# Sheet1.net
KiCad netlist of a schematic drawn in Altium Designer
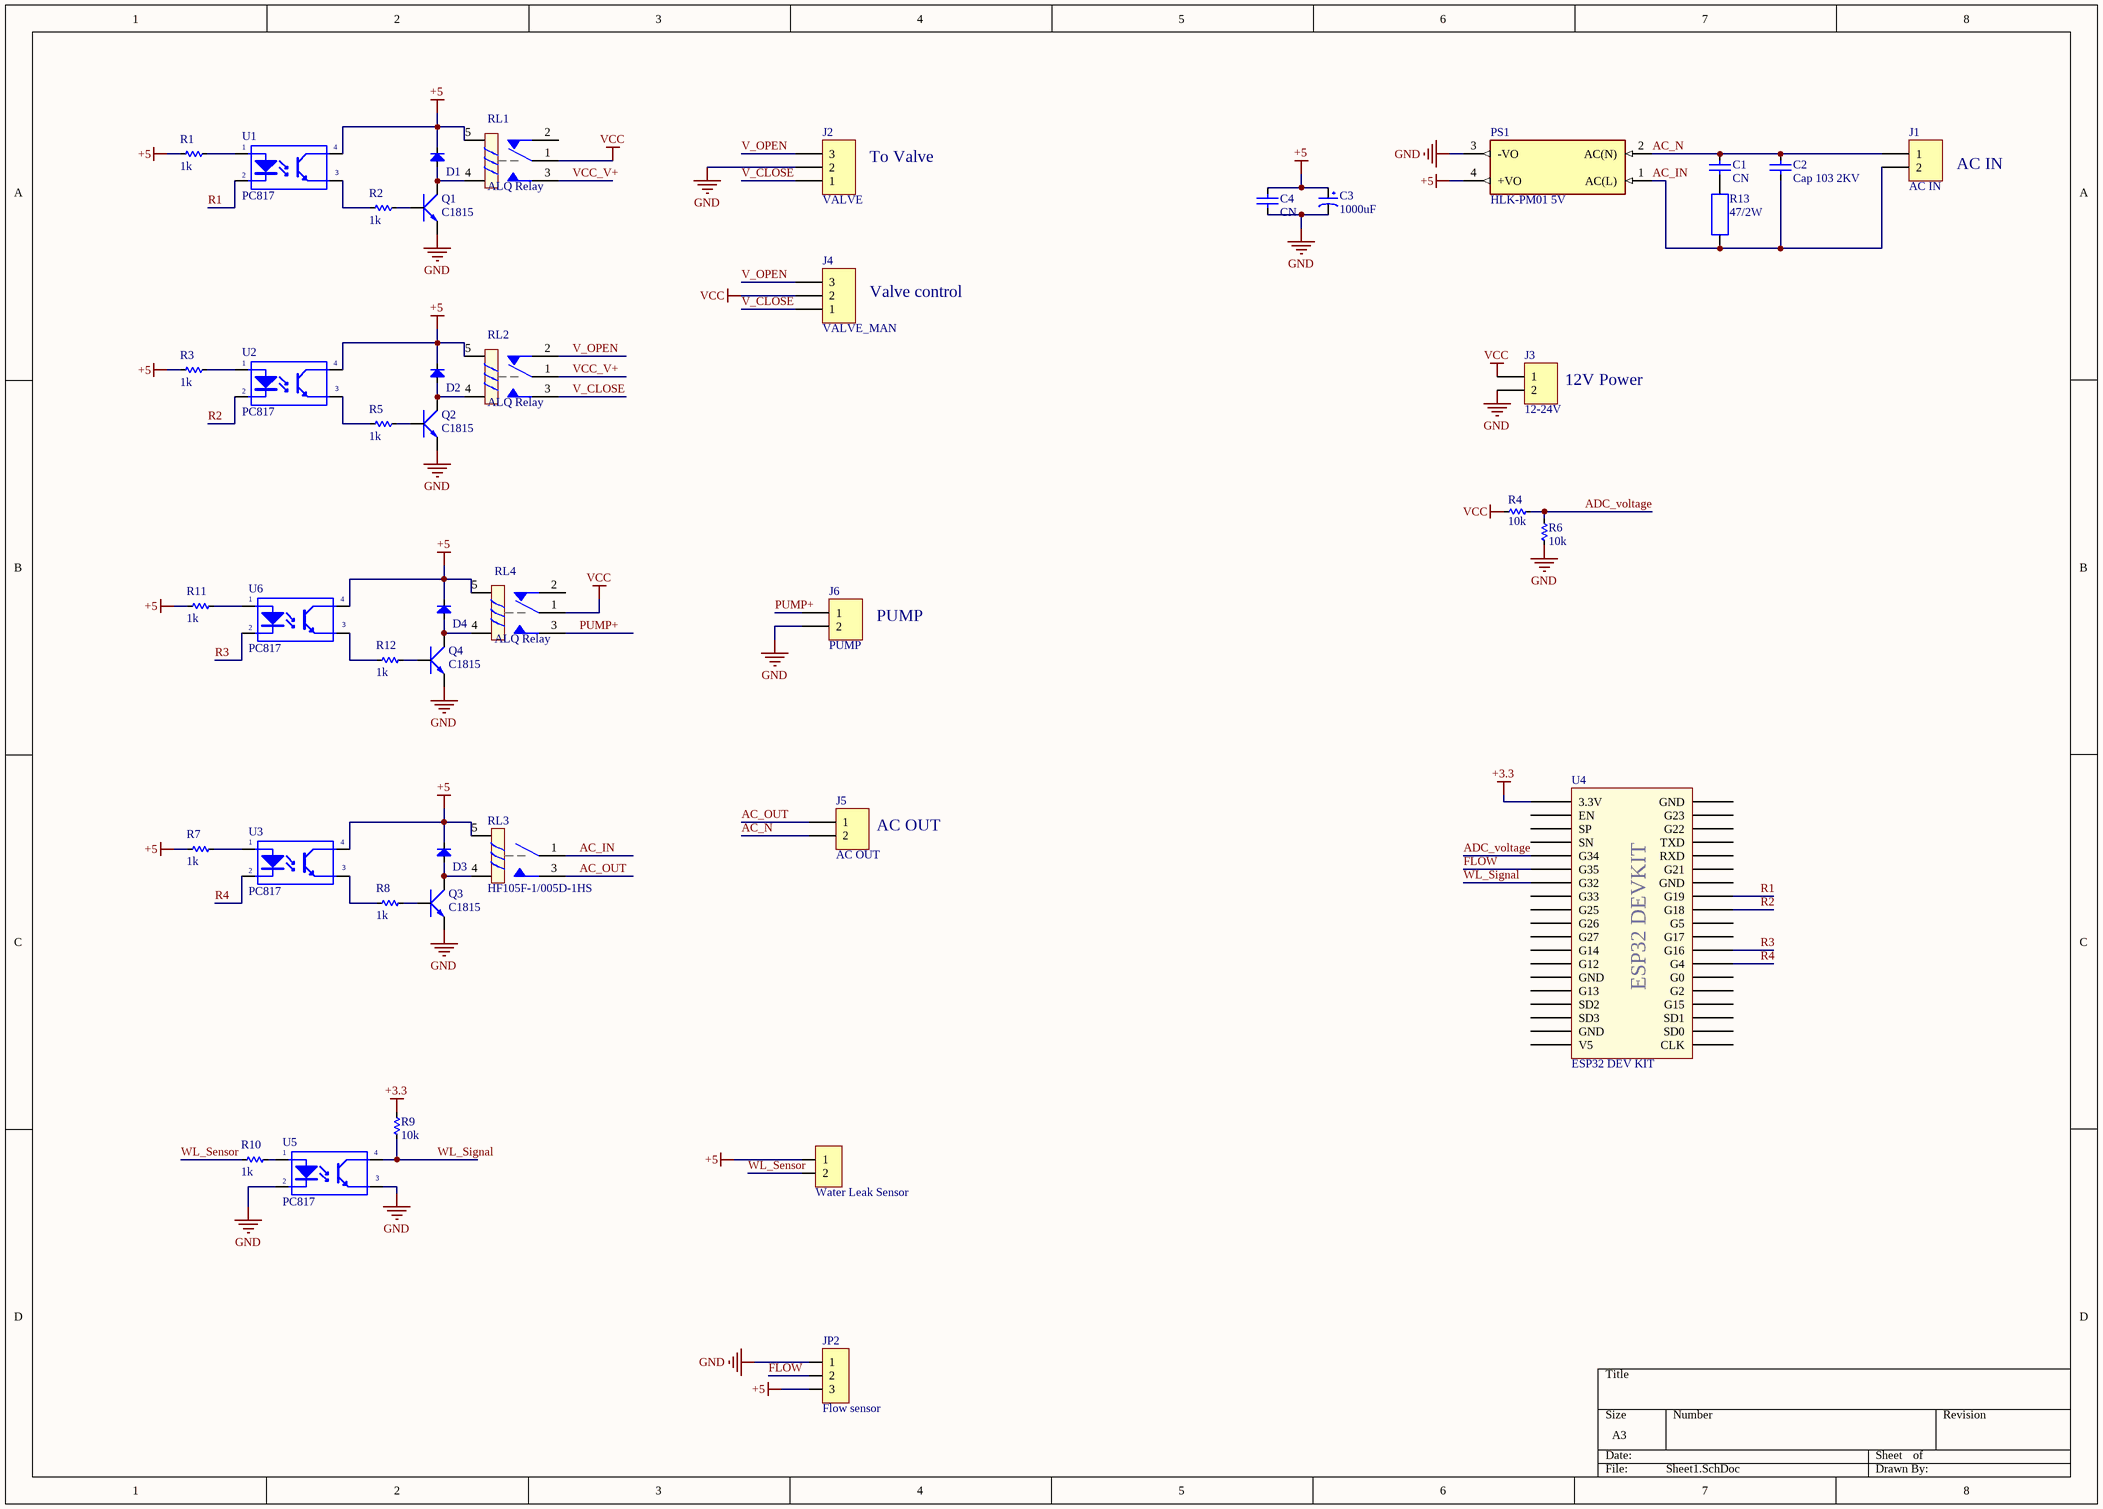
[diagram p0: Sheet1.SchDoc]

(export (version "E")
  (design (tool "Eeschema 10.0.6"))
  (components
    (comp (ref "C1")
      (value "CN")
      (footprint "Cap 15mm")
      (description "Capacitor")
      (libsource (lib "iuh-thuc-hanh") (part "CN"))
    )
    (comp (ref "C2")
      (value "Cap 103 2KV")
      (footprint "Cap 7.5mm")
      (description "Capacitor Ceramic 2KV")
      (libsource (lib "iuh-thuc-hanh") (part "Cap 103 2KV"))
    )
    (comp (ref "C3")
      (value "1000uF")
      (footprint "tu hoa 8mm")
      (description "Cắm")
      (libsource (lib "Altium_Lib_by_KhueNguyenCreator") (part "Tu Hoa 1000uF 16V 8x20"))
    )
    (comp (ref "C4")
      (value "CN")
      (footprint "Cap 2.54mm")
      (description "Capacitor")
      (libsource (lib "iuh-thuc-hanh") (part "CN"))
    )
    (comp (ref "D1")
      (value "Diode")
      (footprint "DIO-1A")
      (description "Default Diode")
      (fields (field (name "PUBLISHER") "Altium Limited"))
      (libsource (lib "LIBRARY1") (part "Diode"))
    )
    (comp (ref "D2")
      (value "Diode")
      (footprint "DIO-1A")
      (description "Default Diode")
      (fields (field (name "PUBLISHER") "Altium Limited"))
      (libsource (lib "LIBRARY1") (part "Diode"))
    )
    (comp (ref "D3")
      (value "Diode")
      (footprint "DIO-1A")
      (description "Default Diode")
      (fields (field (name "PUBLISHER") "Altium Limited"))
      (libsource (lib "LIBRARY1") (part "Diode"))
    )
    (comp (ref "D4")
      (value "Diode")
      (footprint "DIO-1A")
      (description "Default Diode")
      (fields (field (name "PUBLISHER") "Altium Limited"))
      (libsource (lib "LIBRARY1") (part "Diode"))
    )
    (comp (ref "J1")
      (value "AC IN")
      (footprint "CON 2 2EDG5.08")
      (description "CON2 KF terminal")
      (libsource (lib "iuh-thuc-hanh") (part "CON 2 EDG5.08"))
    )
    (comp (ref "J2")
      (value "VALVE")
      (footprint "CON 3 2EDG5.08")
      (description "CON3 KF terminal")
      (libsource (lib "iuh-thuc-hanh") (part "CON 3 EDG5.08"))
    )
    (comp (ref "J3")
      (value "12-24V")
      (footprint "CON 2 2EDG5.08")
      (description "CON2 KF terminal")
      (libsource (lib "iuh-thuc-hanh") (part "CON 2 EDG5.08"))
    )
    (comp (ref "J4")
      (value "VALVE_MAN")
      (footprint "CON 3 2EDG5.08")
      (description "CON3 KF terminal")
      (libsource (lib "iuh-thuc-hanh") (part "CON 3 EDG5.08"))
    )
    (comp (ref "J5")
      (value "AC OUT")
      (footprint "CON 2 2EDG5.08")
      (description "CON2 KF terminal")
      (libsource (lib "iuh-thuc-hanh") (part "CON 2 EDG5.08"))
    )
    (comp (ref "J6")
      (value "PUMP")
      (footprint "CON 2 2EDG5.08")
      (description "CON2 KF terminal")
      (libsource (lib "iuh-thuc-hanh") (part "CON 2 EDG5.08"))
    )
    (comp (ref "JP1")
      (value "Water Leak Sensor")
      (footprint "JP 1x2 CT")
      (description "Cắm")
      (libsource (lib "Altium_Lib_by_KhueNguyenCreator") (part "JP 1x2 2.54 Cai Thang"))
    )
    (comp (ref "JP2")
      (value "Flow sensor")
      (footprint "JP 1x3 DT")
      (description "Cắm")
      (libsource (lib "Altium_Lib_by_KhueNguyenCreator") (part "JP 1x3 2.54 Duc Thang"))
    )
    (comp (ref "PS1")
      (value "HLK-PM01 5V")
      (footprint "CONV_HLK-PM01")
      (description "220VAC to 5V 3W")
      (fields (field (name "MF") "Hi-link") (field (name "MP") "HLK-20M12"))
      (libsource (lib "iuh-thuc-hanh") (part "CONV HLK-PM01"))
    )
    (comp (ref "Q1")
      (value "C1815")
      (footprint "TO92")
      (description "NPN transistor")
      (libsource (lib "Altium_Lib_by_KhueNguyenCreator") (part "Trans C1815 DIP"))
    )
    (comp (ref "Q2")
      (value "C1815")
      (footprint "TO92")
      (description "NPN transistor")
      (libsource (lib "Altium_Lib_by_KhueNguyenCreator") (part "Trans C1815 DIP"))
    )
    (comp (ref "Q3")
      (value "C1815")
      (footprint "TO92")
      (description "NPN transistor")
      (libsource (lib "Altium_Lib_by_KhueNguyenCreator") (part "Trans C1815 DIP"))
    )
    (comp (ref "Q4")
      (value "C1815")
      (footprint "TO92")
      (description "NPN transistor")
      (libsource (lib "Altium_Lib_by_KhueNguyenCreator") (part "Trans C1815 DIP"))
    )
    (comp (ref "R1")
      (value "1k")
      (footprint "RES-1/4W")
      (description "Res")
      (fields
        (field (name "MANUFACTURER") "Generic Components")
        (field (name "PUBLISHER") "Altium Hobart Technology Centre")
      )
      (libsource (lib "LIBRARY1") (part "Res"))
    )
    (comp (ref "R2")
      (value "1k")
      (footprint "RES-1/4W")
      (description "Res")
      (fields
        (field (name "MANUFACTURER") "Generic Components")
        (field (name "PUBLISHER") "Altium Hobart Technology Centre")
      )
      (libsource (lib "LIBRARY1") (part "Res"))
    )
    (comp (ref "R3")
      (value "1k")
      (footprint "RES-1/4W")
      (description "Res")
      (fields
        (field (name "MANUFACTURER") "Generic Components")
        (field (name "PUBLISHER") "Altium Hobart Technology Centre")
      )
      (libsource (lib "LIBRARY1") (part "Res"))
    )
    (comp (ref "R4")
      (value "10k")
      (footprint "RES-1/4W")
      (description "Res")
      (fields
        (field (name "MANUFACTURER") "Generic Components")
        (field (name "PUBLISHER") "Altium Hobart Technology Centre")
      )
      (libsource (lib "LIBRARY1") (part "Res"))
    )
    (comp (ref "R5")
      (value "1k")
      (footprint "RES-1/4W")
      (description "Res")
      (fields
        (field (name "MANUFACTURER") "Generic Components")
        (field (name "PUBLISHER") "Altium Hobart Technology Centre")
      )
      (libsource (lib "LIBRARY1") (part "Res"))
    )
    (comp (ref "R6")
      (value "10k")
      (footprint "RES-1/4W")
      (description "Res")
      (fields
        (field (name "MANUFACTURER") "Generic Components")
        (field (name "PUBLISHER") "Altium Hobart Technology Centre")
      )
      (libsource (lib "LIBRARY1") (part "Res"))
    )
    (comp (ref "R7")
      (value "1k")
      (footprint "RES-1/4W")
      (description "Res")
      (fields
        (field (name "MANUFACTURER") "Generic Components")
        (field (name "PUBLISHER") "Altium Hobart Technology Centre")
      )
      (libsource (lib "LIBRARY1") (part "Res"))
    )
    (comp (ref "R8")
      (value "1k")
      (footprint "RES-1/4W")
      (description "Res")
      (fields
        (field (name "MANUFACTURER") "Generic Components")
        (field (name "PUBLISHER") "Altium Hobart Technology Centre")
      )
      (libsource (lib "LIBRARY1") (part "Res"))
    )
    (comp (ref "R9")
      (value "10k")
      (footprint "RES-1/4W")
      (description "Res")
      (fields
        (field (name "MANUFACTURER") "Generic Components")
        (field (name "PUBLISHER") "Altium Hobart Technology Centre")
      )
      (libsource (lib "LIBRARY1") (part "Res"))
    )
    (comp (ref "R10")
      (value "1k")
      (footprint "RES-1/4W")
      (description "Res")
      (fields
        (field (name "MANUFACTURER") "Generic Components")
        (field (name "PUBLISHER") "Altium Hobart Technology Centre")
      )
      (libsource (lib "LIBRARY1") (part "Res"))
    )
    (comp (ref "R11")
      (value "1k")
      (footprint "RES-1/4W")
      (description "Res")
      (fields
        (field (name "MANUFACTURER") "Generic Components")
        (field (name "PUBLISHER") "Altium Hobart Technology Centre")
      )
      (libsource (lib "LIBRARY1") (part "Res"))
    )
    (comp (ref "R12")
      (value "1k")
      (footprint "RES-1/4W")
      (description "Res")
      (fields
        (field (name "MANUFACTURER") "Generic Components")
        (field (name "PUBLISHER") "Altium Hobart Technology Centre")
      )
      (libsource (lib "LIBRARY1") (part "Res"))
    )
    (comp (ref "R13")
      (value "47/2W")
      (footprint "R2WD")
      (description "Resistor 2W")
      (libsource (lib "iuh-thuc-hanh") (part "R2W"))
    )
    (comp (ref "RL1")
      (value "ALQ Relay")
      (footprint "Relay-LQ-form-C")
      (description "ALQ Relay 10A")
      (libsource (lib "iuh-thuc-hanh") (part "Relay Panasonic LQ"))
    )
    (comp (ref "RL2")
      (value "ALQ Relay")
      (footprint "Relay-LQ-form-C")
      (description "ALQ Relay 10A")
      (libsource (lib "iuh-thuc-hanh") (part "Relay Panasonic LQ"))
    )
    (comp (ref "RL3")
      (value "HF105F-1/005D-1HS")
      (footprint "Relay-HF-30A-Form-A")
      (description "Relay hongfa 30A 4P HF105F-1/005D-1HS")
      (libsource (lib "iuh-thuc-hanh") (part "Relay 30A 4P"))
    )
    (comp (ref "RL4")
      (value "ALQ Relay")
      (footprint "Relay-LQ-form-C")
      (description "ALQ Relay 10A")
      (libsource (lib "iuh-thuc-hanh") (part "Relay Panasonic LQ"))
    )
    (comp (ref "U1")
      (value "PC817")
      (footprint "DIP4")
      (description "Single Opto")
      (libsource (lib "LIBRARY1") (part "PC817"))
    )
    (comp (ref "U2")
      (value "PC817")
      (footprint "DIP4")
      (description "Single Opto")
      (libsource (lib "LIBRARY1") (part "PC817"))
    )
    (comp (ref "U3")
      (value "PC817")
      (footprint "DIP4")
      (description "Single Opto")
      (libsource (lib "LIBRARY1") (part "PC817"))
    )
    (comp (ref "U4")
      (value "ESP32 DEV KIT")
      (footprint "ESP32 DEVKIT")
      (libsource (lib "Altium_Lib_by_KhueNguyenCreator") (part "ESP32 DEV KIT"))
    )
    (comp (ref "U5")
      (value "PC817")
      (footprint "DIP4")
      (description "Single Opto")
      (libsource (lib "LIBRARY1") (part "PC817"))
    )
    (comp (ref "U6")
      (value "PC817")
      (footprint "DIP4")
      (description "Single Opto")
      (libsource (lib "LIBRARY1") (part "PC817"))
    )
  )
  (nets
    (net (code "1") (name "+3.3") (class "Default")
      (node (ref "R9") (pin "2") (pinfunction "2_2") (pintype "passive"))
      (node (ref "U4") (pin "1") (pinfunction "3.3V_1") (pintype "passive"))
    )
    (net (code "2") (name "+5") (class "Default")
      (node (ref "C3") (pin "1") (pinfunction "1_1") (pintype "passive"))
      (node (ref "C4") (pin "2") (pinfunction "2_2") (pintype "passive"))
      (node (ref "D1") (pin "2") (pinfunction "K_2") (pintype "passive"))
      (node (ref "D2") (pin "2") (pinfunction "K_2") (pintype "passive"))
      (node (ref "D3") (pin "2") (pinfunction "K_2") (pintype "passive"))
      (node (ref "D4") (pin "2") (pinfunction "K_2") (pintype "passive"))
      (node (ref "JP1") (pin "1") (pinfunction "1_1") (pintype "passive"))
      (node (ref "JP2") (pin "3") (pinfunction "3_3") (pintype "passive"))
      (node (ref "PS1") (pin "4") (pinfunction "+VO_4") (pintype "output"))
      (node (ref "R1") (pin "1") (pinfunction "1_1") (pintype "passive"))
      (node (ref "R11") (pin "1") (pinfunction "1_1") (pintype "passive"))
      (node (ref "R3") (pin "1") (pinfunction "1_1") (pintype "passive"))
      (node (ref "R7") (pin "1") (pinfunction "1_1") (pintype "passive"))
      (node (ref "RL1") (pin "5") (pinfunction "5_5") (pintype "passive"))
      (node (ref "RL2") (pin "5") (pinfunction "5_5") (pintype "passive"))
      (node (ref "RL3") (pin "5") (pinfunction "5_5") (pintype "passive"))
      (node (ref "RL4") (pin "5") (pinfunction "5_5") (pintype "passive"))
      (node (ref "U1") (pin "4") (pinfunction "C_4") (pintype "passive"))
      (node (ref "U2") (pin "4") (pinfunction "C_4") (pintype "passive"))
      (node (ref "U3") (pin "4") (pinfunction "C_4") (pintype "passive"))
      (node (ref "U6") (pin "4") (pinfunction "C_4") (pintype "passive"))
    )
    (net (code "3") (name "/AC_IN") (class "Default")
      (node (ref "C2") (pin "2") (pinfunction "2_2") (pintype "passive"))
      (node (ref "J1") (pin "2") (pinfunction "2_2") (pintype "passive"))
      (node (ref "PS1") (pin "1") (pinfunction "AC(L)_1") (pintype "input"))
      (node (ref "R13") (pin "2") (pinfunction "2_2") (pintype "passive"))
      (node (ref "RL3") (pin "1") (pinfunction "1_1") (pintype "passive"))
    )
    (net (code "4") (name "/AC_N") (class "Default")
      (node (ref "C1") (pin "2") (pinfunction "2_2") (pintype "passive"))
      (node (ref "C2") (pin "1") (pinfunction "1_1") (pintype "passive"))
      (node (ref "J1") (pin "1") (pinfunction "1_1") (pintype "passive"))
      (node (ref "J5") (pin "2") (pinfunction "2_2") (pintype "passive"))
      (node (ref "PS1") (pin "2") (pinfunction "AC(N)_2") (pintype "input"))
    )
    (net (code "5") (name "/AC_OUT") (class "Default")
      (node (ref "J5") (pin "1") (pinfunction "1_1") (pintype "passive"))
      (node (ref "RL3") (pin "3") (pinfunction "3_3") (pintype "passive"))
    )
    (net (code "6") (name "/ADC_voltage") (class "Default")
      (node (ref "R4") (pin "1") (pinfunction "1_1") (pintype "passive"))
      (node (ref "R6") (pin "2") (pinfunction "2_2") (pintype "passive"))
      (node (ref "U4") (pin "5") (pinfunction "G34_5") (pintype "passive"))
    )
    (net (code "7") (name "/FLOW") (class "Default")
      (node (ref "JP2") (pin "2") (pinfunction "2_2") (pintype "passive"))
      (node (ref "U4") (pin "6") (pinfunction "G35_6") (pintype "passive"))
    )
    (net (code "8") (name "/PUMP+") (class "Default")
      (node (ref "J6") (pin "1") (pinfunction "1_1") (pintype "passive"))
      (node (ref "RL4") (pin "3") (pinfunction "3_3") (pintype "passive"))
    )
    (net (code "9") (name "/R1") (class "Default")
      (node (ref "U1") (pin "2") (pinfunction "K_2") (pintype "passive"))
      (node (ref "U4") (pin "31") (pinfunction "G19_31") (pintype "passive"))
    )
    (net (code "10") (name "/R2") (class "Default")
      (node (ref "U2") (pin "2") (pinfunction "K_2") (pintype "passive"))
      (node (ref "U4") (pin "30") (pinfunction "G18_30") (pintype "passive"))
    )
    (net (code "11") (name "/R3") (class "Default")
      (node (ref "U4") (pin "27") (pinfunction "G16_27") (pintype "passive"))
      (node (ref "U6") (pin "2") (pinfunction "K_2") (pintype "passive"))
    )
    (net (code "12") (name "/R4") (class "Default")
      (node (ref "U3") (pin "2") (pinfunction "K_2") (pintype "passive"))
      (node (ref "U4") (pin "26") (pinfunction "G4_26") (pintype "passive"))
    )
    (net (code "13") (name "/VCC_V+") (class "Default")
      (node (ref "RL1") (pin "3") (pinfunction "3_3") (pintype "passive"))
      (node (ref "RL2") (pin "1") (pinfunction "1_1") (pintype "passive"))
    )
    (net (code "14") (name "/V_CLOSE") (class "Default")
      (node (ref "J2") (pin "1") (pinfunction "1_1") (pintype "passive"))
      (node (ref "J4") (pin "1") (pinfunction "1_1") (pintype "passive"))
      (node (ref "RL2") (pin "3") (pinfunction "3_3") (pintype "passive"))
    )
    (net (code "15") (name "/V_OPEN") (class "Default")
      (node (ref "J2") (pin "3") (pinfunction "3_3") (pintype "passive"))
      (node (ref "J4") (pin "3") (pinfunction "3_3") (pintype "passive"))
      (node (ref "RL2") (pin "2") (pinfunction "2_2") (pintype "passive"))
    )
    (net (code "16") (name "/WL_Sensor") (class "Default")
      (node (ref "JP1") (pin "2") (pinfunction "2_2") (pintype "passive"))
      (node (ref "R10") (pin "1") (pinfunction "1_1") (pintype "passive"))
    )
    (net (code "17") (name "/WL_Signal") (class "Default")
      (node (ref "R9") (pin "1") (pinfunction "1_1") (pintype "passive"))
      (node (ref "U4") (pin "7") (pinfunction "G32_7") (pintype "passive"))
      (node (ref "U5") (pin "4") (pinfunction "C_4") (pintype "passive"))
    )
    (net (code "18") (name "GND") (class "Default")
      (node (ref "C3") (pin "2") (pinfunction "2_2") (pintype "passive"))
      (node (ref "C4") (pin "1") (pinfunction "1_1") (pintype "passive"))
      (node (ref "J2") (pin "2") (pinfunction "2_2") (pintype "passive"))
      (node (ref "J3") (pin "2") (pinfunction "2_2") (pintype "passive"))
      (node (ref "J6") (pin "2") (pinfunction "2_2") (pintype "passive"))
      (node (ref "JP2") (pin "1") (pinfunction "1_1") (pintype "passive"))
      (node (ref "PS1") (pin "3") (pinfunction "-VO_3") (pintype "output"))
      (node (ref "Q1") (pin "1") (pinfunction "E_1") (pintype "passive"))
      (node (ref "Q2") (pin "1") (pinfunction "E_1") (pintype "passive"))
      (node (ref "Q3") (pin "1") (pinfunction "E_1") (pintype "passive"))
      (node (ref "Q4") (pin "1") (pinfunction "E_1") (pintype "passive"))
      (node (ref "R6") (pin "1") (pinfunction "1_1") (pintype "passive"))
      (node (ref "U5") (pin "2") (pinfunction "K_2") (pintype "passive"))
      (node (ref "U5") (pin "3") (pinfunction "E_3") (pintype "passive"))
    )
    (net (code "19") (name "Net-(C1-Pad1)") (class "Default")
      (node (ref "C1") (pin "1") (pinfunction "1_1") (pintype "passive"))
      (node (ref "R13") (pin "1") (pinfunction "1_1") (pintype "passive"))
    )
    (net (code "20") (name "Net-(D1-A)") (class "Default")
      (node (ref "D1") (pin "1") (pinfunction "A_1") (pintype "passive"))
      (node (ref "Q1") (pin "2") (pinfunction "C_2") (pintype "passive"))
      (node (ref "RL1") (pin "4") (pinfunction "4_4") (pintype "passive"))
    )
    (net (code "21") (name "Net-(D2-A)") (class "Default")
      (node (ref "D2") (pin "1") (pinfunction "A_1") (pintype "passive"))
      (node (ref "Q2") (pin "2") (pinfunction "C_2") (pintype "passive"))
      (node (ref "RL2") (pin "4") (pinfunction "4_4") (pintype "passive"))
    )
    (net (code "22") (name "Net-(D3-A)") (class "Default")
      (node (ref "D3") (pin "1") (pinfunction "A_1") (pintype "passive"))
      (node (ref "Q3") (pin "2") (pinfunction "C_2") (pintype "passive"))
      (node (ref "RL3") (pin "4") (pinfunction "4_4") (pintype "passive"))
    )
    (net (code "23") (name "Net-(D4-A)") (class "Default")
      (node (ref "D4") (pin "1") (pinfunction "A_1") (pintype "passive"))
      (node (ref "Q4") (pin "2") (pinfunction "C_2") (pintype "passive"))
      (node (ref "RL4") (pin "4") (pinfunction "4_4") (pintype "passive"))
    )
    (net (code "24") (name "Net-(Q1-B)") (class "Default")
      (node (ref "Q1") (pin "3") (pinfunction "B_3") (pintype "passive"))
      (node (ref "R2") (pin "2") (pinfunction "2_2") (pintype "passive"))
    )
    (net (code "25") (name "Net-(Q2-B)") (class "Default")
      (node (ref "Q2") (pin "3") (pinfunction "B_3") (pintype "passive"))
      (node (ref "R5") (pin "2") (pinfunction "2_2") (pintype "passive"))
    )
    (net (code "26") (name "Net-(Q3-B)") (class "Default")
      (node (ref "Q3") (pin "3") (pinfunction "B_3") (pintype "passive"))
      (node (ref "R8") (pin "2") (pinfunction "2_2") (pintype "passive"))
    )
    (net (code "27") (name "Net-(Q4-B)") (class "Default")
      (node (ref "Q4") (pin "3") (pinfunction "B_3") (pintype "passive"))
      (node (ref "R12") (pin "2") (pinfunction "2_2") (pintype "passive"))
    )
    (net (code "28") (name "Net-(U1-A)") (class "Default")
      (node (ref "R1") (pin "2") (pinfunction "2_2") (pintype "passive"))
      (node (ref "U1") (pin "1") (pinfunction "A_1") (pintype "passive"))
    )
    (net (code "29") (name "Net-(U1-E)") (class "Default")
      (node (ref "R2") (pin "1") (pinfunction "1_1") (pintype "passive"))
      (node (ref "U1") (pin "3") (pinfunction "E_3") (pintype "passive"))
    )
    (net (code "30") (name "Net-(U2-A)") (class "Default")
      (node (ref "R3") (pin "2") (pinfunction "2_2") (pintype "passive"))
      (node (ref "U2") (pin "1") (pinfunction "A_1") (pintype "passive"))
    )
    (net (code "31") (name "Net-(U2-E)") (class "Default")
      (node (ref "R5") (pin "1") (pinfunction "1_1") (pintype "passive"))
      (node (ref "U2") (pin "3") (pinfunction "E_3") (pintype "passive"))
    )
    (net (code "32") (name "Net-(U3-A)") (class "Default")
      (node (ref "R7") (pin "2") (pinfunction "2_2") (pintype "passive"))
      (node (ref "U3") (pin "1") (pinfunction "A_1") (pintype "passive"))
    )
    (net (code "33") (name "Net-(U3-E)") (class "Default")
      (node (ref "R8") (pin "1") (pinfunction "1_1") (pintype "passive"))
      (node (ref "U3") (pin "3") (pinfunction "E_3") (pintype "passive"))
    )
    (net (code "34") (name "Net-(U5-A)") (class "Default")
      (node (ref "R10") (pin "2") (pinfunction "2_2") (pintype "passive"))
      (node (ref "U5") (pin "1") (pinfunction "A_1") (pintype "passive"))
    )
    (net (code "35") (name "Net-(U6-A)") (class "Default")
      (node (ref "R11") (pin "2") (pinfunction "2_2") (pintype "passive"))
      (node (ref "U6") (pin "1") (pinfunction "A_1") (pintype "passive"))
    )
    (net (code "36") (name "Net-(U6-E)") (class "Default")
      (node (ref "R12") (pin "1") (pinfunction "1_1") (pintype "passive"))
      (node (ref "U6") (pin "3") (pinfunction "E_3") (pintype "passive"))
    )
    (net (code "37") (name "VCC") (class "Default")
      (node (ref "J3") (pin "1") (pinfunction "1_1") (pintype "passive"))
      (node (ref "J4") (pin "2") (pinfunction "2_2") (pintype "passive"))
      (node (ref "R4") (pin "2") (pinfunction "2_2") (pintype "passive"))
      (node (ref "RL1") (pin "1") (pinfunction "1_1") (pintype "passive"))
      (node (ref "RL4") (pin "1") (pinfunction "1_1") (pintype "passive"))
    )
    (net (code "38") (name "unconnected-(RL1-Pad2)") (class "Default")
      (node (ref "RL1") (pin "2") (pinfunction "2_2") (pintype "passive"))
    )
    (net (code "39") (name "unconnected-(RL4-Pad2)") (class "Default")
      (node (ref "RL4") (pin "2") (pinfunction "2_2") (pintype "passive"))
    )
    (net (code "40") (name "unconnected-(U4-CLK-Pad20)") (class "Default")
      (node (ref "U4") (pin "20") (pinfunction "CLK_20") (pintype "passive"))
    )
    (net (code "41") (name "unconnected-(U4-EN-Pad2)") (class "Default")
      (node (ref "U4") (pin "2") (pinfunction "EN_2") (pintype "passive"))
    )
    (net (code "42") (name "unconnected-(U4-G0-Pad25)") (class "Default")
      (node (ref "U4") (pin "25") (pinfunction "G0_25") (pintype "passive"))
    )
    (net (code "43") (name "unconnected-(U4-G2-Pad24)") (class "Default")
      (node (ref "U4") (pin "24") (pinfunction "G2_24") (pintype "passive"))
    )
    (net (code "44") (name "unconnected-(U4-G5-Pad29)") (class "Default")
      (node (ref "U4") (pin "29") (pinfunction "G5_29") (pintype "passive"))
    )
    (net (code "45") (name "unconnected-(U4-G12-Pad13)") (class "Default")
      (node (ref "U4") (pin "13") (pinfunction "G12_13") (pintype "passive"))
    )
    (net (code "46") (name "unconnected-(U4-G13-Pad15)") (class "Default")
      (node (ref "U4") (pin "15") (pinfunction "G13_15") (pintype "passive"))
    )
    (net (code "47") (name "unconnected-(U4-G14-Pad12)") (class "Default")
      (node (ref "U4") (pin "12") (pinfunction "G14_12") (pintype "passive"))
    )
    (net (code "48") (name "unconnected-(U4-G15-Pad23)") (class "Default")
      (node (ref "U4") (pin "23") (pinfunction "G15_23") (pintype "passive"))
    )
    (net (code "49") (name "unconnected-(U4-G17-Pad28)") (class "Default")
      (node (ref "U4") (pin "28") (pinfunction "G17_28") (pintype "passive"))
    )
    (net (code "50") (name "unconnected-(U4-G21-Pad33)") (class "Default")
      (node (ref "U4") (pin "33") (pinfunction "G21_33") (pintype "passive"))
    )
    (net (code "51") (name "unconnected-(U4-G22-Pad36)") (class "Default")
      (node (ref "U4") (pin "36") (pinfunction "G22_36") (pintype "passive"))
    )
    (net (code "52") (name "unconnected-(U4-G23-Pad37)") (class "Default")
      (node (ref "U4") (pin "37") (pinfunction "G23_37") (pintype "passive"))
    )
    (net (code "53") (name "unconnected-(U4-G25-Pad9)") (class "Default")
      (node (ref "U4") (pin "9") (pinfunction "G25_9") (pintype "passive"))
    )
    (net (code "54") (name "unconnected-(U4-G26-Pad10)") (class "Default")
      (node (ref "U4") (pin "10") (pinfunction "G26_10") (pintype "passive"))
    )
    (net (code "55") (name "unconnected-(U4-G27-Pad11)") (class "Default")
      (node (ref "U4") (pin "11") (pinfunction "G27_11") (pintype "passive"))
    )
    (net (code "56") (name "unconnected-(U4-G33-Pad8)") (class "Default")
      (node (ref "U4") (pin "8") (pinfunction "G33_8") (pintype "passive"))
    )
    (net (code "57") (name "unconnected-(U4-GND-Pad14)") (class "Default")
      (node (ref "U4") (pin "14") (pinfunction "GND_14") (pintype "passive"))
    )
    (net (code "58") (name "unconnected-(U4-GND-Pad18)") (class "Default")
      (node (ref "U4") (pin "18") (pinfunction "GND_18") (pintype "passive"))
    )
    (net (code "59") (name "unconnected-(U4-GND-Pad32)") (class "Default")
      (node (ref "U4") (pin "32") (pinfunction "GND_32") (pintype "passive"))
    )
    (net (code "60") (name "unconnected-(U4-GND-Pad38)") (class "Default")
      (node (ref "U4") (pin "38") (pinfunction "GND_38") (pintype "passive"))
    )
    (net (code "61") (name "unconnected-(U4-RXD-Pad34)") (class "Default")
      (node (ref "U4") (pin "34") (pinfunction "RXD_34") (pintype "passive"))
    )
    (net (code "62") (name "unconnected-(U4-SD0-Pad21)") (class "Default")
      (node (ref "U4") (pin "21") (pinfunction "SD0_21") (pintype "passive"))
    )
    (net (code "63") (name "unconnected-(U4-SD1-Pad22)") (class "Default")
      (node (ref "U4") (pin "22") (pinfunction "SD1_22") (pintype "passive"))
    )
    (net (code "64") (name "unconnected-(U4-SD2-Pad16)") (class "Default")
      (node (ref "U4") (pin "16") (pinfunction "SD2_16") (pintype "passive"))
    )
    (net (code "65") (name "unconnected-(U4-SD3-Pad17)") (class "Default")
      (node (ref "U4") (pin "17") (pinfunction "SD3_17") (pintype "passive"))
    )
    (net (code "66") (name "unconnected-(U4-SN-Pad4)") (class "Default")
      (node (ref "U4") (pin "4") (pinfunction "SN_4") (pintype "passive"))
    )
    (net (code "67") (name "unconnected-(U4-SP-Pad3)") (class "Default")
      (node (ref "U4") (pin "3") (pinfunction "SP_3") (pintype "passive"))
    )
    (net (code "68") (name "unconnected-(U4-TXD-Pad35)") (class "Default")
      (node (ref "U4") (pin "35") (pinfunction "TXD_35") (pintype "passive"))
    )
    (net (code "69") (name "unconnected-(U4-V5-Pad19)") (class "Default")
      (node (ref "U4") (pin "19") (pinfunction "V5_19") (pintype "passive"))
    )
  )
)
